# MultiSensor_CPS.net
KiCad netlist of a schematic drawn in EAGLE
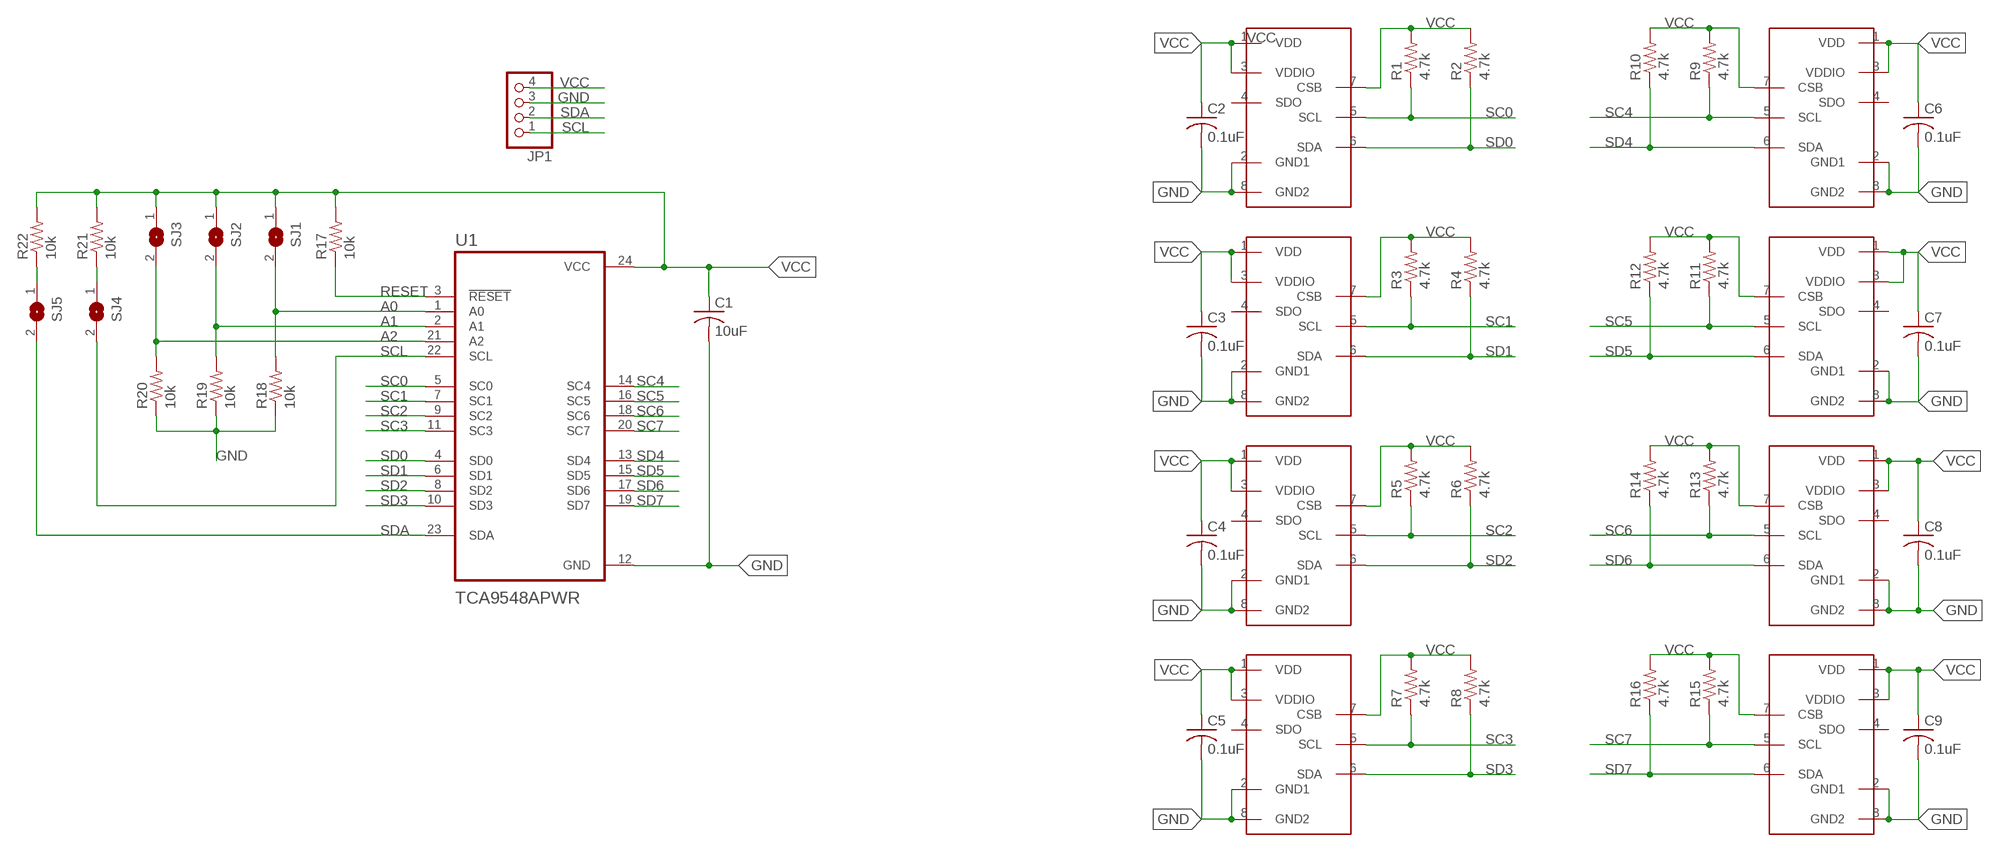
[diagram p0: schematic, sheet 1]

(export (version "E")
  (design (tool "Eeschema 10.0.6"))
  (components
    (comp (ref "B1")
      (value "CPS123")
      (footprint "eagle-import:CPS123")
      (libsource (lib "eagle-import") (part "CPS123"))
    )
    (comp (ref "B2")
      (value "CPS123")
      (footprint "eagle-import:CPS123")
      (libsource (lib "eagle-import") (part "CPS123"))
    )
    (comp (ref "B3")
      (value "CPS123")
      (footprint "eagle-import:CPS123")
      (libsource (lib "eagle-import") (part "CPS123"))
    )
    (comp (ref "B4")
      (value "CPS123")
      (footprint "eagle-import:CPS123")
      (libsource (lib "eagle-import") (part "CPS123"))
    )
    (comp (ref "B5")
      (value "CPS123")
      (footprint "eagle-import:CPS123")
      (libsource (lib "eagle-import") (part "CPS123"))
    )
    (comp (ref "B6")
      (value "CPS123")
      (footprint "eagle-import:CPS123")
      (libsource (lib "eagle-import") (part "CPS123"))
    )
    (comp (ref "B8")
      (value "CPS123")
      (footprint "eagle-import:CPS123")
      (libsource (lib "eagle-import") (part "CPS123"))
    )
    (comp (ref "B9")
      (value "CPS123")
      (footprint "eagle-import:CPS123")
      (libsource (lib "eagle-import") (part "CPS123"))
    )
    (comp (ref "C1")
      (value "10uF")
      (footprint "eagle-import:C0805")
      (libsource (lib "eagle-import") (part "C-USC0805"))
    )
    (comp (ref "C2")
      (value "0.1uF")
      (footprint "eagle-import:C0805")
      (libsource (lib "eagle-import") (part "C-USC0805"))
    )
    (comp (ref "C3")
      (value "0.1uF")
      (footprint "eagle-import:C0805")
      (libsource (lib "eagle-import") (part "C-USC0805"))
    )
    (comp (ref "C4")
      (value "0.1uF")
      (footprint "eagle-import:C0805")
      (libsource (lib "eagle-import") (part "C-USC0805"))
    )
    (comp (ref "C5")
      (value "0.1uF")
      (footprint "eagle-import:C0805")
      (libsource (lib "eagle-import") (part "C-USC0805"))
    )
    (comp (ref "C6")
      (value "0.1uF")
      (footprint "eagle-import:C0805")
      (libsource (lib "eagle-import") (part "C-USC0805"))
    )
    (comp (ref "C7")
      (value "0.1uF")
      (footprint "eagle-import:C0805")
      (libsource (lib "eagle-import") (part "C-USC0805"))
    )
    (comp (ref "C8")
      (value "0.1uF")
      (footprint "eagle-import:C0805")
      (libsource (lib "eagle-import") (part "C-USC0805"))
    )
    (comp (ref "C9")
      (value "0.1uF")
      (footprint "eagle-import:C0805")
      (libsource (lib "eagle-import") (part "C-USC0805"))
    )
    (comp (ref "JP1")
      (value "PINHD-1X4")
      (footprint "eagle-import:1X04")
      (libsource (lib "eagle-import") (part "PINHD-1X4"))
    )
    (comp (ref "R1")
      (value "4.7k")
      (footprint "eagle-import:R0805")
      (libsource (lib "eagle-import") (part "R-US_R0805"))
    )
    (comp (ref "R2")
      (value "4.7k")
      (footprint "eagle-import:R0805")
      (libsource (lib "eagle-import") (part "R-US_R0805"))
    )
    (comp (ref "R3")
      (value "4.7k")
      (footprint "eagle-import:R0805")
      (libsource (lib "eagle-import") (part "R-US_R0805"))
    )
    (comp (ref "R4")
      (value "4.7k")
      (footprint "eagle-import:R0805")
      (libsource (lib "eagle-import") (part "R-US_R0805"))
    )
    (comp (ref "R5")
      (value "4.7k")
      (footprint "eagle-import:R0805")
      (libsource (lib "eagle-import") (part "R-US_R0805"))
    )
    (comp (ref "R6")
      (value "4.7k")
      (footprint "eagle-import:R0805")
      (libsource (lib "eagle-import") (part "R-US_R0805"))
    )
    (comp (ref "R7")
      (value "4.7k")
      (footprint "eagle-import:R0805")
      (libsource (lib "eagle-import") (part "R-US_R0805"))
    )
    (comp (ref "R8")
      (value "4.7k")
      (footprint "eagle-import:R0805")
      (libsource (lib "eagle-import") (part "R-US_R0805"))
    )
    (comp (ref "R9")
      (value "4.7k")
      (footprint "eagle-import:R0805")
      (libsource (lib "eagle-import") (part "R-US_R0805"))
    )
    (comp (ref "R10")
      (value "4.7k")
      (footprint "eagle-import:R0805")
      (libsource (lib "eagle-import") (part "R-US_R0805"))
    )
    (comp (ref "R11")
      (value "4.7k")
      (footprint "eagle-import:R0805")
      (libsource (lib "eagle-import") (part "R-US_R0805"))
    )
    (comp (ref "R12")
      (value "4.7k")
      (footprint "eagle-import:R0805")
      (libsource (lib "eagle-import") (part "R-US_R0805"))
    )
    (comp (ref "R13")
      (value "4.7k")
      (footprint "eagle-import:R0805")
      (libsource (lib "eagle-import") (part "R-US_R0805"))
    )
    (comp (ref "R14")
      (value "4.7k")
      (footprint "eagle-import:R0805")
      (libsource (lib "eagle-import") (part "R-US_R0805"))
    )
    (comp (ref "R15")
      (value "4.7k")
      (footprint "eagle-import:R0805")
      (libsource (lib "eagle-import") (part "R-US_R0805"))
    )
    (comp (ref "R16")
      (value "4.7k")
      (footprint "eagle-import:R0805")
      (libsource (lib "eagle-import") (part "R-US_R0805"))
    )
    (comp (ref "R17")
      (value "10k")
      (footprint "eagle-import:R0805")
      (libsource (lib "eagle-import") (part "R-US_R0805"))
    )
    (comp (ref "R18")
      (value "10k")
      (footprint "eagle-import:R0805")
      (libsource (lib "eagle-import") (part "R-US_R0805"))
    )
    (comp (ref "R19")
      (value "10k")
      (footprint "eagle-import:R0805")
      (libsource (lib "eagle-import") (part "R-US_R0805"))
    )
    (comp (ref "R20")
      (value "10k")
      (footprint "eagle-import:R0805")
      (libsource (lib "eagle-import") (part "R-US_R0805"))
    )
    (comp (ref "R21")
      (value "10k")
      (footprint "eagle-import:R0805")
      (libsource (lib "eagle-import") (part "R-US_R0805"))
    )
    (comp (ref "R22")
      (value "10k")
      (footprint "eagle-import:R0805")
      (libsource (lib "eagle-import") (part "R-US_R0805"))
    )
    (comp (ref "SJ1") (value "SJ") (footprint "eagle-import:SJ") (libsource (lib "eagle-import") (part "SJ")))
    (comp (ref "SJ2") (value "SJ") (footprint "eagle-import:SJ") (libsource (lib "eagle-import") (part "SJ")))
    (comp (ref "SJ3") (value "SJ") (footprint "eagle-import:SJ") (libsource (lib "eagle-import") (part "SJ")))
    (comp (ref "SJ4") (value "SJ") (footprint "eagle-import:SJ") (libsource (lib "eagle-import") (part "SJ")))
    (comp (ref "SJ5") (value "SJ") (footprint "eagle-import:SJ") (libsource (lib "eagle-import") (part "SJ")))
    (comp (ref "U1")
      (value "TCA9548APWR")
      (footprint "eagle-import:SOP65P640X120-24N")
      (fields (field (name "DIGI-KEY_PART_NUMBER") "296-34905-1-ND") (field (name "MF") "Texas Instruments"))
      (libsource (lib "eagle-import") (part "TCA9548APWR"))
    )
  )
  (nets
    (net (code "1") (name "/A0") (class "Default")
      (node (ref "R18") (pin "2") (pinfunction "2_2") (pintype "passive"))
      (node (ref "SJ1") (pin "2") (pinfunction "2_2") (pintype "passive"))
      (node (ref "U1") (pin "1") (pinfunction "A0_1") (pintype "input"))
    )
    (net (code "2") (name "/A1") (class "Default")
      (node (ref "R19") (pin "2") (pinfunction "2_2") (pintype "passive"))
      (node (ref "SJ2") (pin "2") (pinfunction "2_2") (pintype "passive"))
      (node (ref "U1") (pin "2") (pinfunction "A1_2") (pintype "input"))
    )
    (net (code "3") (name "/A2") (class "Default")
      (node (ref "R20") (pin "2") (pinfunction "2_2") (pintype "passive"))
      (node (ref "SJ3") (pin "2") (pinfunction "2_2") (pintype "passive"))
      (node (ref "U1") (pin "21") (pinfunction "A2_21") (pintype "input"))
    )
    (net (code "4") (name "/RESET") (class "Default")
      (node (ref "R17") (pin "1") (pinfunction "1_1") (pintype "passive"))
      (node (ref "U1") (pin "3") (pinfunction "~{RESET}_3") (pintype "input"))
    )
    (net (code "5") (name "/SC0") (class "Default")
      (node (ref "B5") (pin "5") (pinfunction "SCL_5") (pintype "bidirectional"))
      (node (ref "R1") (pin "1") (pinfunction "1_1") (pintype "passive"))
      (node (ref "U1") (pin "5") (pinfunction "SC0_5") (pintype "bidirectional"))
    )
    (net (code "6") (name "/SC1") (class "Default")
      (node (ref "B1") (pin "5") (pinfunction "SCL_5") (pintype "bidirectional"))
      (node (ref "R3") (pin "1") (pinfunction "1_1") (pintype "passive"))
      (node (ref "U1") (pin "7") (pinfunction "SC1_7") (pintype "bidirectional"))
    )
    (net (code "7") (name "/SC2") (class "Default")
      (node (ref "B2") (pin "5") (pinfunction "SCL_5") (pintype "bidirectional"))
      (node (ref "R5") (pin "1") (pinfunction "1_1") (pintype "passive"))
      (node (ref "U1") (pin "9") (pinfunction "SC2_9") (pintype "bidirectional"))
    )
    (net (code "8") (name "/SC3") (class "Default")
      (node (ref "B9") (pin "5") (pinfunction "SCL_5") (pintype "bidirectional"))
      (node (ref "R7") (pin "1") (pinfunction "1_1") (pintype "passive"))
      (node (ref "U1") (pin "11") (pinfunction "SC3_11") (pintype "bidirectional"))
    )
    (net (code "9") (name "/SC4") (class "Default")
      (node (ref "B6") (pin "5") (pinfunction "SCL_5") (pintype "bidirectional"))
      (node (ref "R9") (pin "1") (pinfunction "1_1") (pintype "passive"))
      (node (ref "U1") (pin "14") (pinfunction "SC4_14") (pintype "bidirectional"))
    )
    (net (code "10") (name "/SC5") (class "Default")
      (node (ref "B4") (pin "5") (pinfunction "SCL_5") (pintype "bidirectional"))
      (node (ref "R11") (pin "1") (pinfunction "1_1") (pintype "passive"))
      (node (ref "U1") (pin "16") (pinfunction "SC5_16") (pintype "bidirectional"))
    )
    (net (code "11") (name "/SC6") (class "Default")
      (node (ref "B3") (pin "5") (pinfunction "SCL_5") (pintype "bidirectional"))
      (node (ref "R13") (pin "1") (pinfunction "1_1") (pintype "passive"))
      (node (ref "U1") (pin "18") (pinfunction "SC6_18") (pintype "bidirectional"))
    )
    (net (code "12") (name "/SC7") (class "Default")
      (node (ref "B8") (pin "5") (pinfunction "SCL_5") (pintype "bidirectional"))
      (node (ref "R15") (pin "1") (pinfunction "1_1") (pintype "passive"))
      (node (ref "U1") (pin "20") (pinfunction "SC7_20") (pintype "bidirectional"))
    )
    (net (code "13") (name "/SCL") (class "Default")
      (node (ref "JP1") (pin "1") (pinfunction "1_1") (pintype "passive"))
      (node (ref "SJ4") (pin "2") (pinfunction "2_2") (pintype "passive"))
      (node (ref "U1") (pin "22") (pinfunction "SCL_22") (pintype "input"))
    )
    (net (code "14") (name "/SD0") (class "Default")
      (node (ref "B5") (pin "6") (pinfunction "SDA_6") (pintype "bidirectional"))
      (node (ref "R2") (pin "1") (pinfunction "1_1") (pintype "passive"))
      (node (ref "U1") (pin "4") (pinfunction "SD0_4") (pintype "bidirectional"))
    )
    (net (code "15") (name "/SD1") (class "Default")
      (node (ref "B1") (pin "6") (pinfunction "SDA_6") (pintype "bidirectional"))
      (node (ref "R4") (pin "1") (pinfunction "1_1") (pintype "passive"))
      (node (ref "U1") (pin "6") (pinfunction "SD1_6") (pintype "bidirectional"))
    )
    (net (code "16") (name "/SD2") (class "Default")
      (node (ref "B2") (pin "6") (pinfunction "SDA_6") (pintype "bidirectional"))
      (node (ref "R6") (pin "1") (pinfunction "1_1") (pintype "passive"))
      (node (ref "U1") (pin "8") (pinfunction "SD2_8") (pintype "bidirectional"))
    )
    (net (code "17") (name "/SD3") (class "Default")
      (node (ref "B9") (pin "6") (pinfunction "SDA_6") (pintype "bidirectional"))
      (node (ref "R8") (pin "1") (pinfunction "1_1") (pintype "passive"))
      (node (ref "U1") (pin "10") (pinfunction "SD3_10") (pintype "bidirectional"))
    )
    (net (code "18") (name "/SD4") (class "Default")
      (node (ref "B6") (pin "6") (pinfunction "SDA_6") (pintype "bidirectional"))
      (node (ref "R10") (pin "1") (pinfunction "1_1") (pintype "passive"))
      (node (ref "U1") (pin "13") (pinfunction "SD4_13") (pintype "bidirectional"))
    )
    (net (code "19") (name "/SD5") (class "Default")
      (node (ref "B4") (pin "6") (pinfunction "SDA_6") (pintype "bidirectional"))
      (node (ref "R12") (pin "1") (pinfunction "1_1") (pintype "passive"))
      (node (ref "U1") (pin "15") (pinfunction "SD5_15") (pintype "bidirectional"))
    )
    (net (code "20") (name "/SD6") (class "Default")
      (node (ref "B3") (pin "6") (pinfunction "SDA_6") (pintype "bidirectional"))
      (node (ref "R14") (pin "1") (pinfunction "1_1") (pintype "passive"))
      (node (ref "U1") (pin "17") (pinfunction "SD6_17") (pintype "bidirectional"))
    )
    (net (code "21") (name "/SD7") (class "Default")
      (node (ref "B8") (pin "6") (pinfunction "SDA_6") (pintype "bidirectional"))
      (node (ref "R16") (pin "1") (pinfunction "1_1") (pintype "passive"))
      (node (ref "U1") (pin "19") (pinfunction "SD7_19") (pintype "bidirectional"))
    )
    (net (code "22") (name "/SDA") (class "Default")
      (node (ref "JP1") (pin "2") (pinfunction "2_2") (pintype "passive"))
      (node (ref "SJ5") (pin "2") (pinfunction "2_2") (pintype "passive"))
      (node (ref "U1") (pin "23") (pinfunction "SDA_23") (pintype "bidirectional"))
    )
    (net (code "23") (name "GND") (class "Default")
      (node (ref "B1") (pin "2") (pinfunction "GND1_2") (pintype "bidirectional"))
      (node (ref "B1") (pin "8") (pinfunction "GND2_8") (pintype "bidirectional"))
      (node (ref "B2") (pin "2") (pinfunction "GND1_2") (pintype "bidirectional"))
      (node (ref "B2") (pin "8") (pinfunction "GND2_8") (pintype "bidirectional"))
      (node (ref "B3") (pin "2") (pinfunction "GND1_2") (pintype "bidirectional"))
      (node (ref "B3") (pin "8") (pinfunction "GND2_8") (pintype "bidirectional"))
      (node (ref "B4") (pin "2") (pinfunction "GND1_2") (pintype "bidirectional"))
      (node (ref "B4") (pin "8") (pinfunction "GND2_8") (pintype "bidirectional"))
      (node (ref "B5") (pin "2") (pinfunction "GND1_2") (pintype "bidirectional"))
      (node (ref "B5") (pin "8") (pinfunction "GND2_8") (pintype "bidirectional"))
      (node (ref "B6") (pin "2") (pinfunction "GND1_2") (pintype "bidirectional"))
      (node (ref "B6") (pin "8") (pinfunction "GND2_8") (pintype "bidirectional"))
      (node (ref "B8") (pin "2") (pinfunction "GND1_2") (pintype "bidirectional"))
      (node (ref "B8") (pin "8") (pinfunction "GND2_8") (pintype "bidirectional"))
      (node (ref "B9") (pin "2") (pinfunction "GND1_2") (pintype "bidirectional"))
      (node (ref "B9") (pin "8") (pinfunction "GND2_8") (pintype "bidirectional"))
      (node (ref "C1") (pin "2") (pinfunction "2_2") (pintype "passive"))
      (node (ref "C2") (pin "2") (pinfunction "2_2") (pintype "passive"))
      (node (ref "C3") (pin "2") (pinfunction "2_2") (pintype "passive"))
      (node (ref "C4") (pin "2") (pinfunction "2_2") (pintype "passive"))
      (node (ref "C5") (pin "2") (pinfunction "2_2") (pintype "passive"))
      (node (ref "C6") (pin "2") (pinfunction "2_2") (pintype "passive"))
      (node (ref "C7") (pin "2") (pinfunction "2_2") (pintype "passive"))
      (node (ref "C8") (pin "2") (pinfunction "2_2") (pintype "passive"))
      (node (ref "C9") (pin "2") (pinfunction "2_2") (pintype "passive"))
      (node (ref "JP1") (pin "3") (pinfunction "3_3") (pintype "passive"))
      (node (ref "R18") (pin "1") (pinfunction "1_1") (pintype "passive"))
      (node (ref "R19") (pin "1") (pinfunction "1_1") (pintype "passive"))
      (node (ref "R20") (pin "1") (pinfunction "1_1") (pintype "passive"))
      (node (ref "U1") (pin "12") (pinfunction "GND_12") (pintype "power_in"))
    )
    (net (code "24") (name "Net-(R21-Pad1)") (class "Default")
      (node (ref "R21") (pin "1") (pinfunction "1_1") (pintype "passive"))
      (node (ref "SJ4") (pin "1") (pinfunction "1_1") (pintype "passive"))
    )
    (net (code "25") (name "Net-(R22-Pad1)") (class "Default")
      (node (ref "R22") (pin "1") (pinfunction "1_1") (pintype "passive"))
      (node (ref "SJ5") (pin "1") (pinfunction "1_1") (pintype "passive"))
    )
    (net (code "26") (name "VCC") (class "Default")
      (node (ref "B1") (pin "1") (pinfunction "VDD_1") (pintype "bidirectional"))
      (node (ref "B1") (pin "3") (pinfunction "VDDIO_3") (pintype "bidirectional"))
      (node (ref "B1") (pin "7") (pinfunction "CSB_7") (pintype "bidirectional"))
      (node (ref "B2") (pin "1") (pinfunction "VDD_1") (pintype "bidirectional"))
      (node (ref "B2") (pin "3") (pinfunction "VDDIO_3") (pintype "bidirectional"))
      (node (ref "B2") (pin "7") (pinfunction "CSB_7") (pintype "bidirectional"))
      (node (ref "B3") (pin "1") (pinfunction "VDD_1") (pintype "bidirectional"))
      (node (ref "B3") (pin "3") (pinfunction "VDDIO_3") (pintype "bidirectional"))
      (node (ref "B3") (pin "7") (pinfunction "CSB_7") (pintype "bidirectional"))
      (node (ref "B4") (pin "1") (pinfunction "VDD_1") (pintype "bidirectional"))
      (node (ref "B4") (pin "3") (pinfunction "VDDIO_3") (pintype "bidirectional"))
      (node (ref "B4") (pin "7") (pinfunction "CSB_7") (pintype "bidirectional"))
      (node (ref "B5") (pin "1") (pinfunction "VDD_1") (pintype "bidirectional"))
      (node (ref "B5") (pin "3") (pinfunction "VDDIO_3") (pintype "bidirectional"))
      (node (ref "B5") (pin "7") (pinfunction "CSB_7") (pintype "bidirectional"))
      (node (ref "B6") (pin "1") (pinfunction "VDD_1") (pintype "bidirectional"))
      (node (ref "B6") (pin "3") (pinfunction "VDDIO_3") (pintype "bidirectional"))
      (node (ref "B6") (pin "7") (pinfunction "CSB_7") (pintype "bidirectional"))
      (node (ref "B8") (pin "1") (pinfunction "VDD_1") (pintype "bidirectional"))
      (node (ref "B8") (pin "3") (pinfunction "VDDIO_3") (pintype "bidirectional"))
      (node (ref "B8") (pin "7") (pinfunction "CSB_7") (pintype "bidirectional"))
      (node (ref "B9") (pin "1") (pinfunction "VDD_1") (pintype "bidirectional"))
      (node (ref "B9") (pin "3") (pinfunction "VDDIO_3") (pintype "bidirectional"))
      (node (ref "B9") (pin "7") (pinfunction "CSB_7") (pintype "bidirectional"))
      (node (ref "C1") (pin "1") (pinfunction "1_1") (pintype "passive"))
      (node (ref "C2") (pin "1") (pinfunction "1_1") (pintype "passive"))
      (node (ref "C3") (pin "1") (pinfunction "1_1") (pintype "passive"))
      (node (ref "C4") (pin "1") (pinfunction "1_1") (pintype "passive"))
      (node (ref "C5") (pin "1") (pinfunction "1_1") (pintype "passive"))
      (node (ref "C6") (pin "1") (pinfunction "1_1") (pintype "passive"))
      (node (ref "C7") (pin "1") (pinfunction "1_1") (pintype "passive"))
      (node (ref "C8") (pin "1") (pinfunction "1_1") (pintype "passive"))
      (node (ref "C9") (pin "1") (pinfunction "1_1") (pintype "passive"))
      (node (ref "JP1") (pin "4") (pinfunction "4_4") (pintype "passive"))
      (node (ref "R1") (pin "2") (pinfunction "2_2") (pintype "passive"))
      (node (ref "R10") (pin "2") (pinfunction "2_2") (pintype "passive"))
      (node (ref "R11") (pin "2") (pinfunction "2_2") (pintype "passive"))
      (node (ref "R12") (pin "2") (pinfunction "2_2") (pintype "passive"))
      (node (ref "R13") (pin "2") (pinfunction "2_2") (pintype "passive"))
      (node (ref "R14") (pin "2") (pinfunction "2_2") (pintype "passive"))
      (node (ref "R15") (pin "2") (pinfunction "2_2") (pintype "passive"))
      (node (ref "R16") (pin "2") (pinfunction "2_2") (pintype "passive"))
      (node (ref "R17") (pin "2") (pinfunction "2_2") (pintype "passive"))
      (node (ref "R2") (pin "2") (pinfunction "2_2") (pintype "passive"))
      (node (ref "R21") (pin "2") (pinfunction "2_2") (pintype "passive"))
      (node (ref "R22") (pin "2") (pinfunction "2_2") (pintype "passive"))
      (node (ref "R3") (pin "2") (pinfunction "2_2") (pintype "passive"))
      (node (ref "R4") (pin "2") (pinfunction "2_2") (pintype "passive"))
      (node (ref "R5") (pin "2") (pinfunction "2_2") (pintype "passive"))
      (node (ref "R6") (pin "2") (pinfunction "2_2") (pintype "passive"))
      (node (ref "R7") (pin "2") (pinfunction "2_2") (pintype "passive"))
      (node (ref "R8") (pin "2") (pinfunction "2_2") (pintype "passive"))
      (node (ref "R9") (pin "2") (pinfunction "2_2") (pintype "passive"))
      (node (ref "SJ1") (pin "1") (pinfunction "1_1") (pintype "passive"))
      (node (ref "SJ2") (pin "1") (pinfunction "1_1") (pintype "passive"))
      (node (ref "SJ3") (pin "1") (pinfunction "1_1") (pintype "passive"))
      (node (ref "U1") (pin "24") (pinfunction "VCC_24") (pintype "power_in"))
    )
    (net (code "27") (name "unconnected-(B1-SDO-Pad4)") (class "Default")
      (node (ref "B1") (pin "4") (pinfunction "SDO_4") (pintype "bidirectional"))
    )
    (net (code "28") (name "unconnected-(B2-SDO-Pad4)") (class "Default")
      (node (ref "B2") (pin "4") (pinfunction "SDO_4") (pintype "bidirectional"))
    )
    (net (code "29") (name "unconnected-(B3-SDO-Pad4)") (class "Default")
      (node (ref "B3") (pin "4") (pinfunction "SDO_4") (pintype "bidirectional"))
    )
    (net (code "30") (name "unconnected-(B4-SDO-Pad4)") (class "Default")
      (node (ref "B4") (pin "4") (pinfunction "SDO_4") (pintype "bidirectional"))
    )
    (net (code "31") (name "unconnected-(B5-SDO-Pad4)") (class "Default")
      (node (ref "B5") (pin "4") (pinfunction "SDO_4") (pintype "bidirectional"))
    )
    (net (code "32") (name "unconnected-(B6-SDO-Pad4)") (class "Default")
      (node (ref "B6") (pin "4") (pinfunction "SDO_4") (pintype "bidirectional"))
    )
    (net (code "33") (name "unconnected-(B8-SDO-Pad4)") (class "Default")
      (node (ref "B8") (pin "4") (pinfunction "SDO_4") (pintype "bidirectional"))
    )
    (net (code "34") (name "unconnected-(B9-SDO-Pad4)") (class "Default")
      (node (ref "B9") (pin "4") (pinfunction "SDO_4") (pintype "bidirectional"))
    )
  )
)
